# box.net
KiCad netlist of a schematic drawn in EAGLE
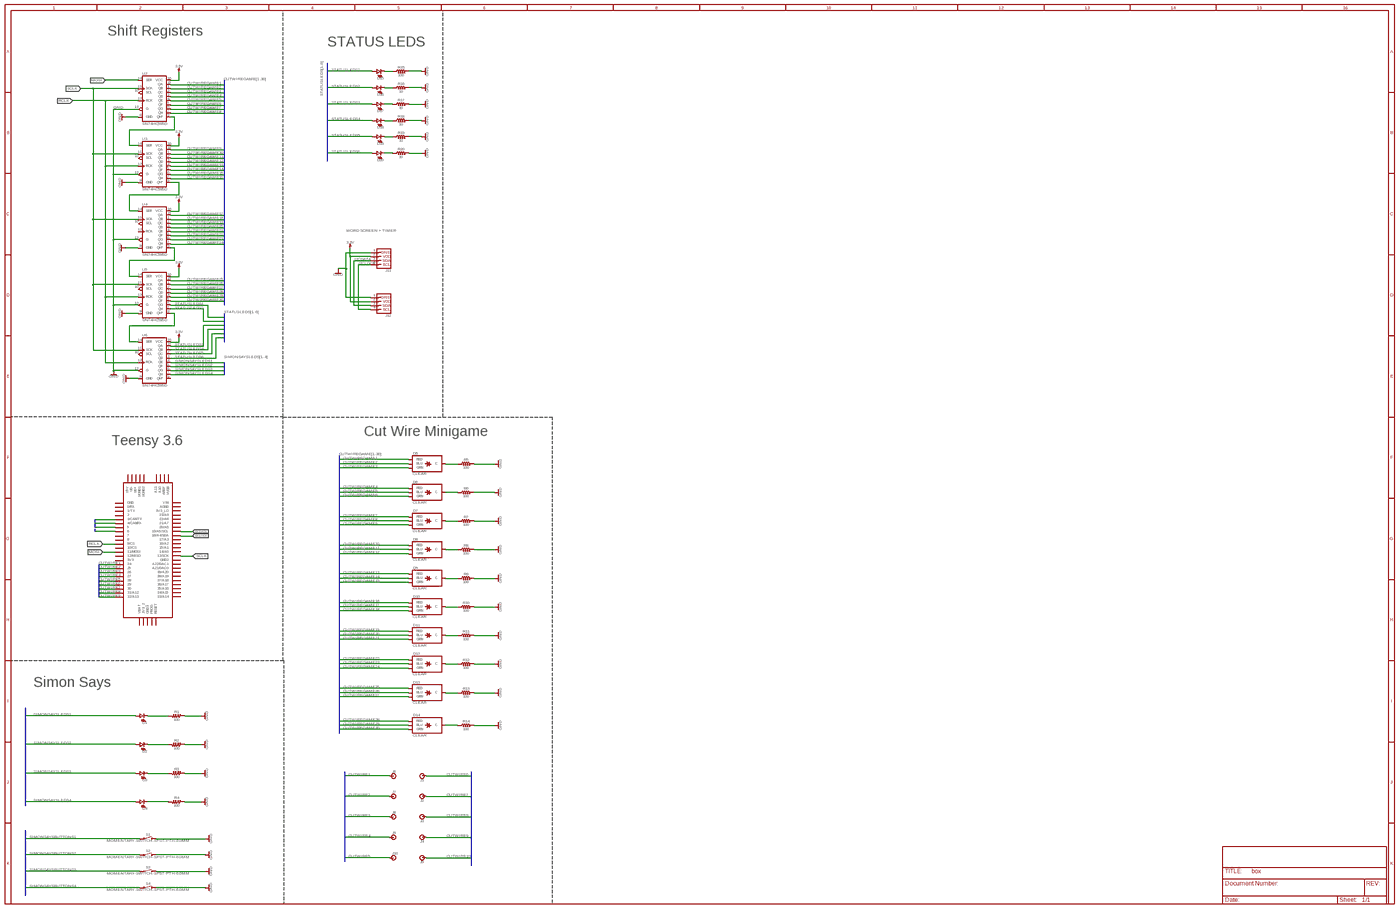
[diagram p0: schematic, sheet 1, overview]
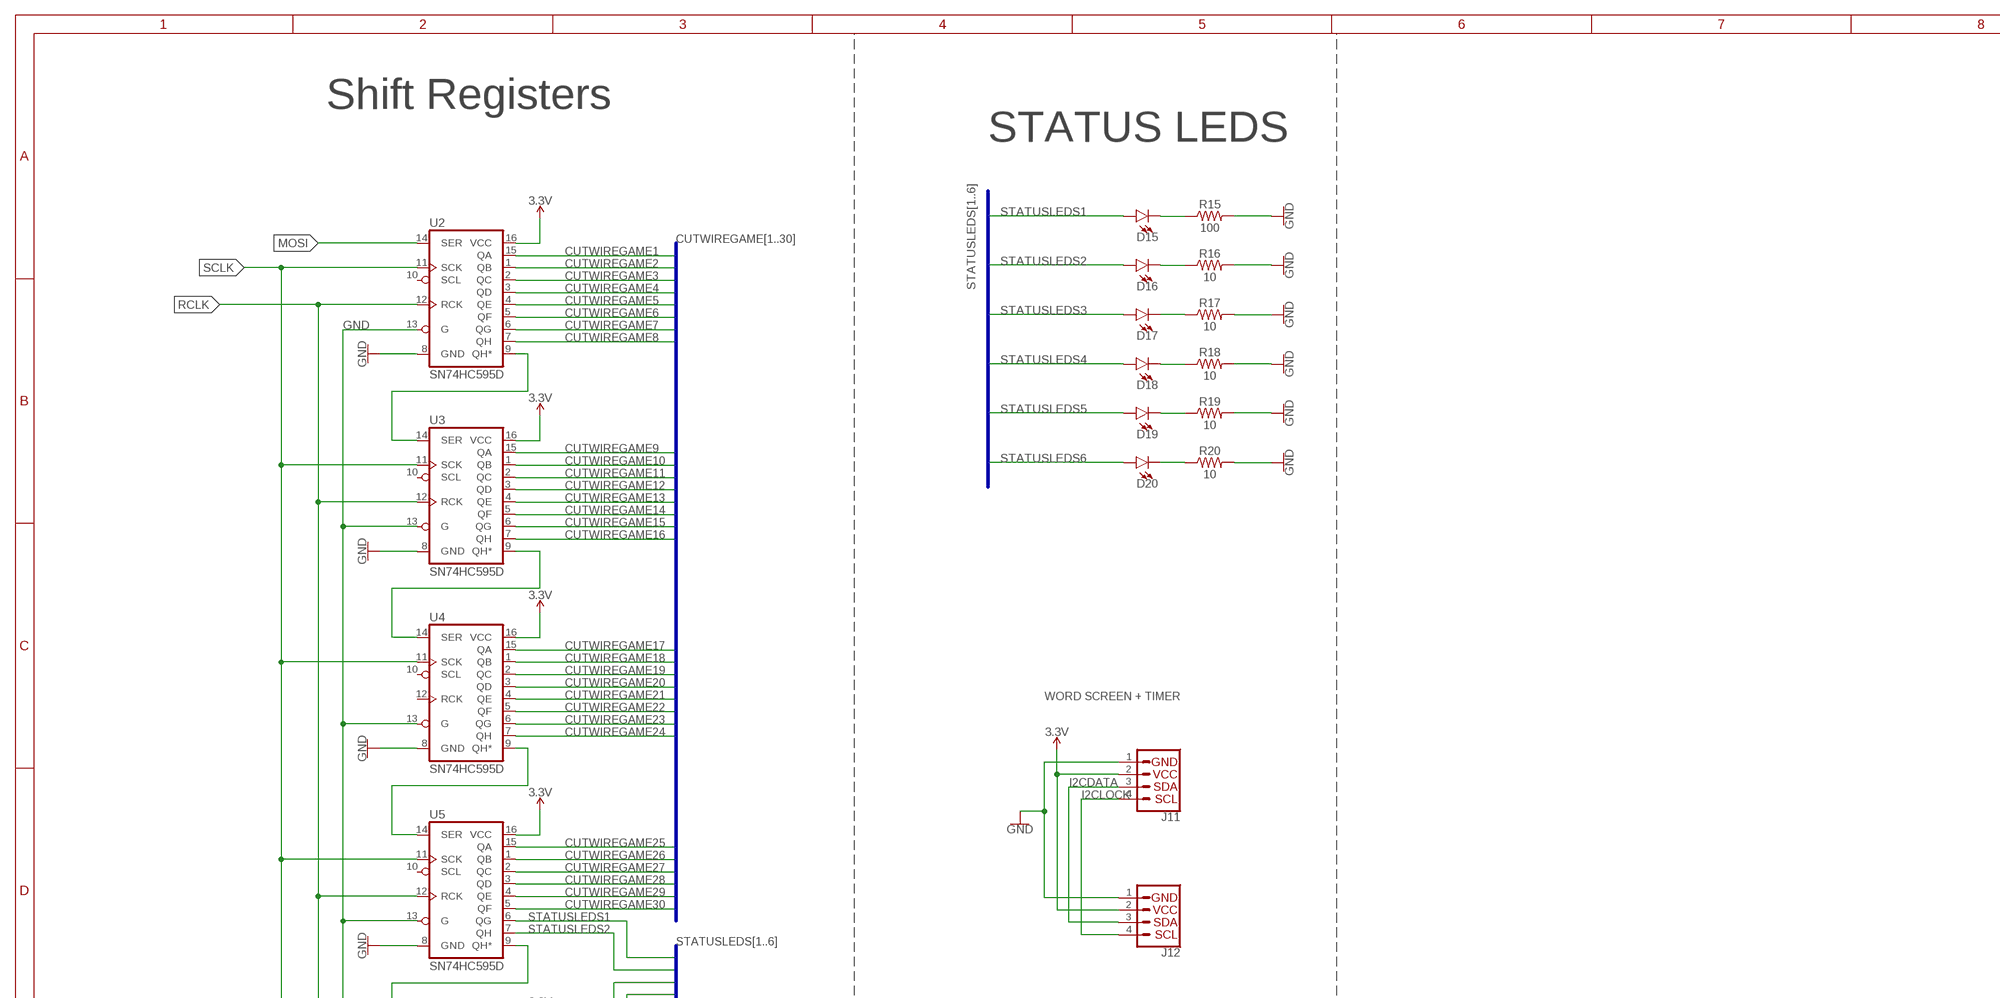
[diagram p1: schematic, sheet 1, part 1 of 4]
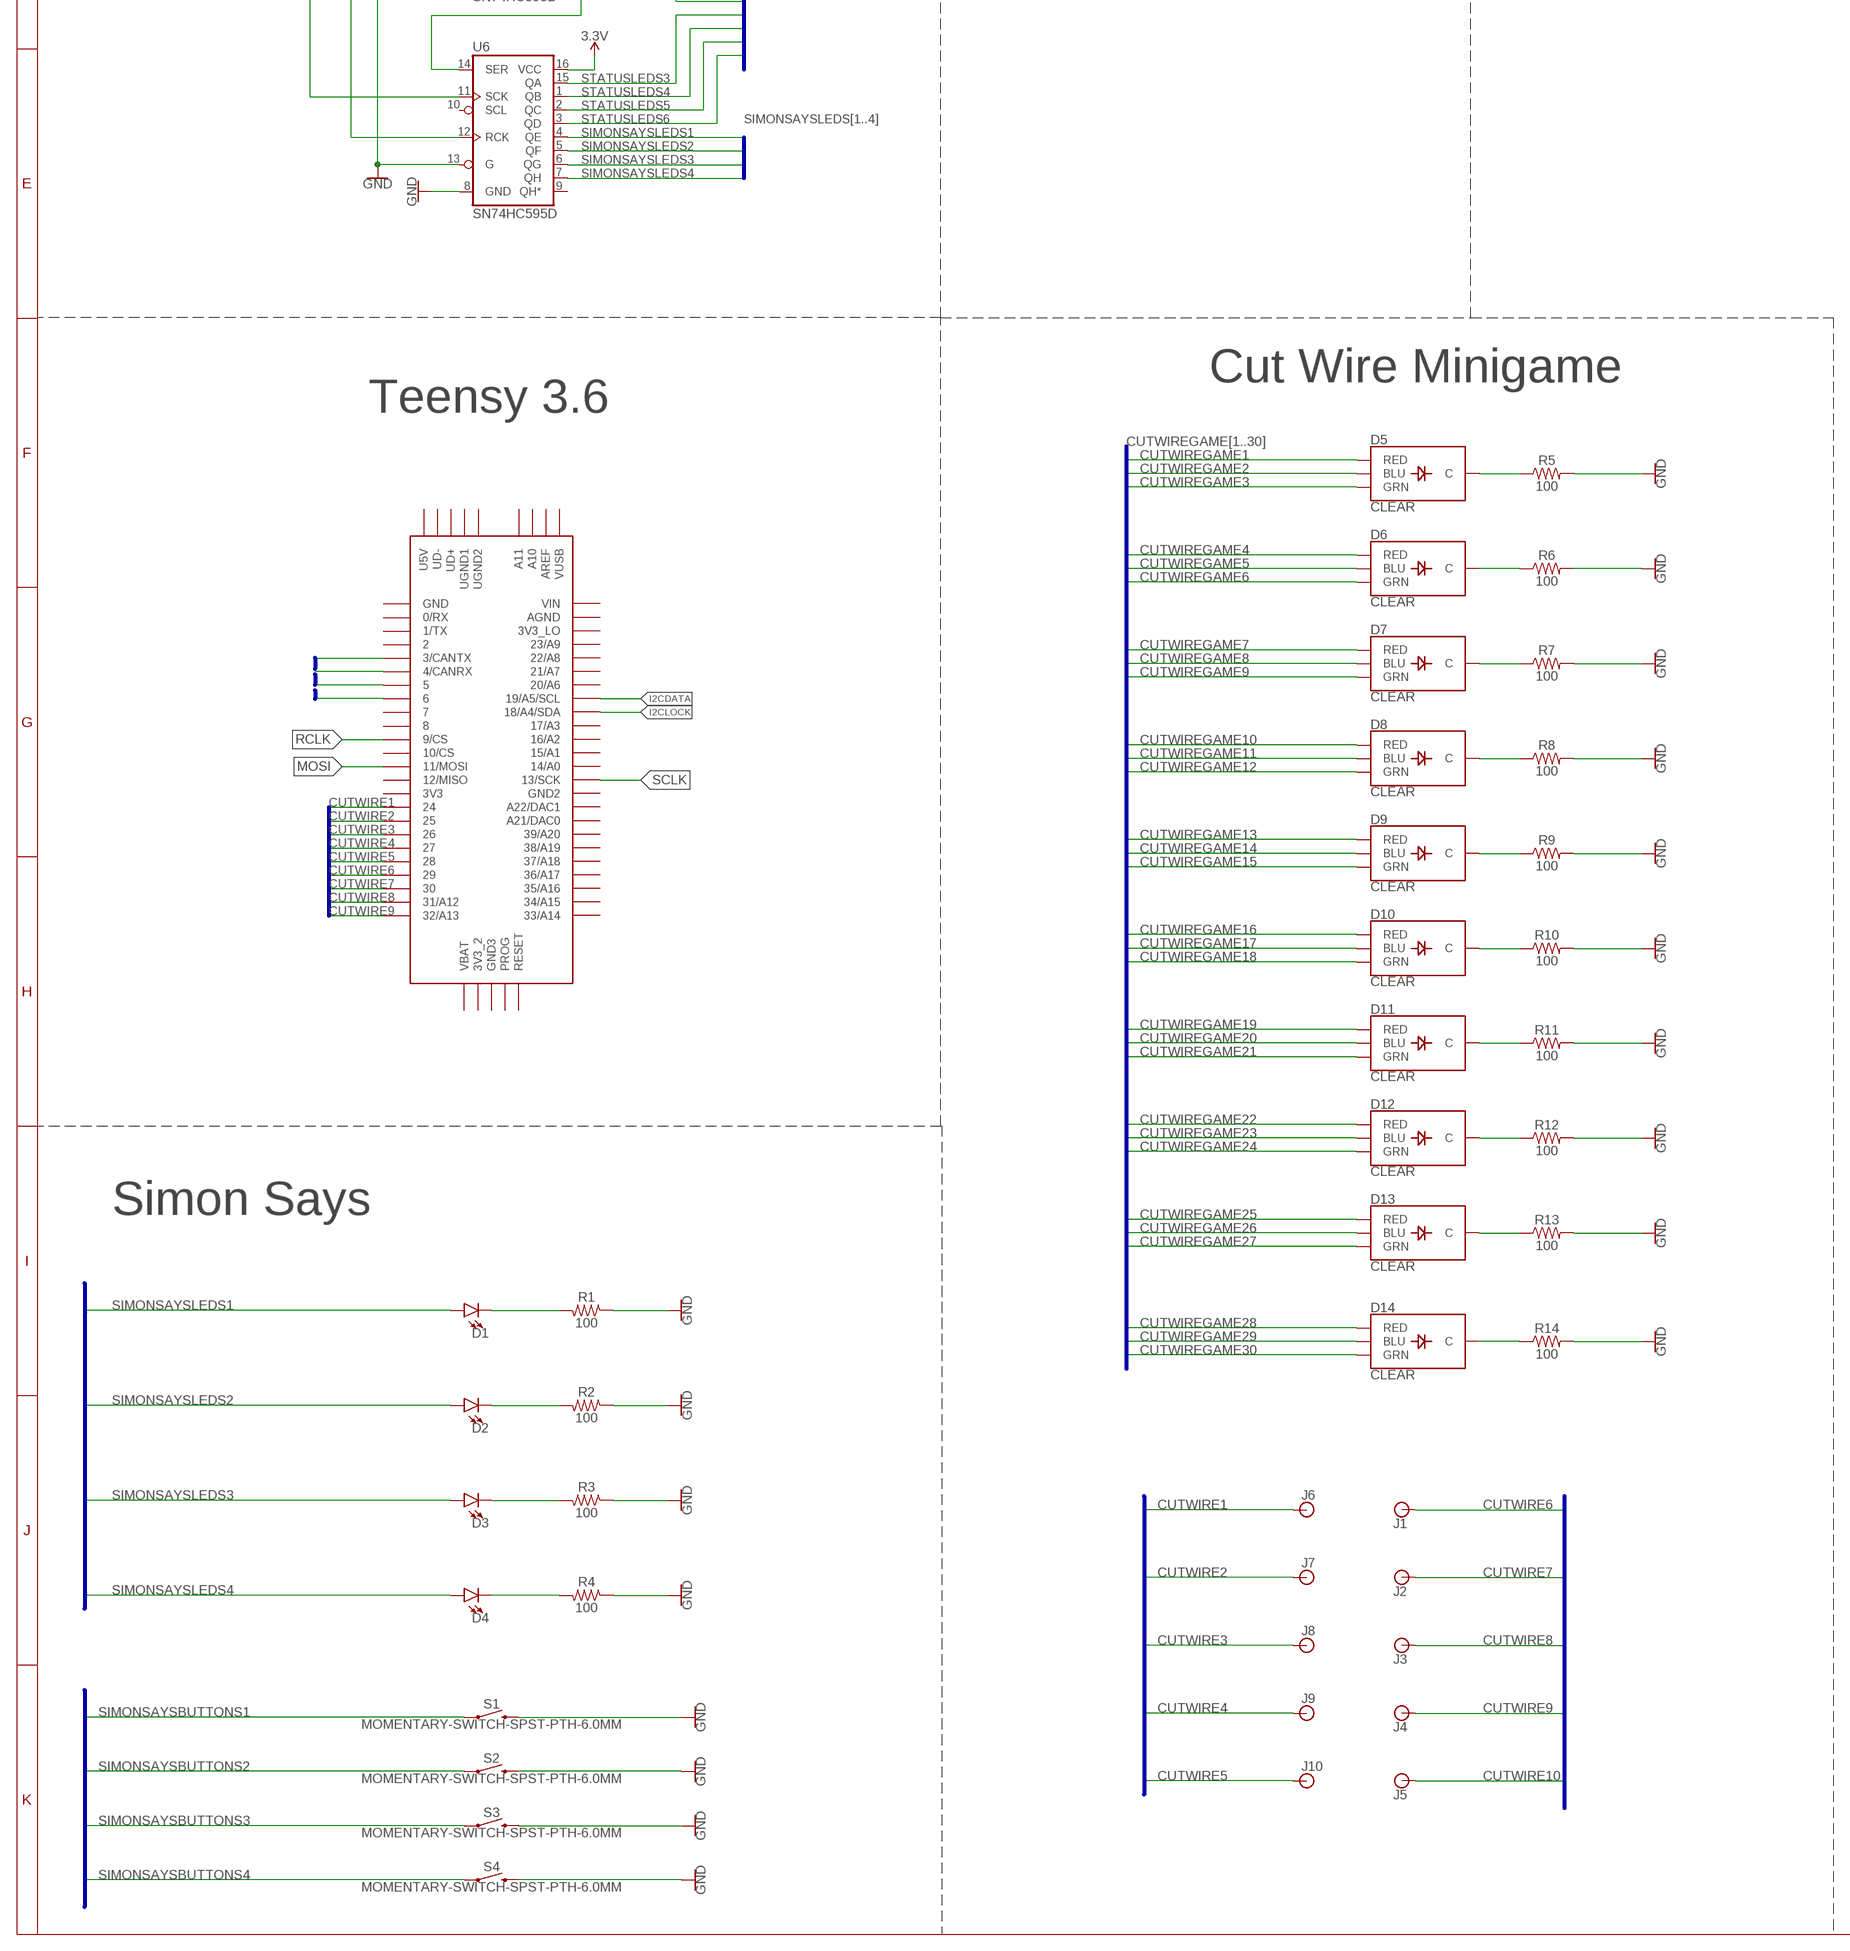
[diagram p2: schematic, sheet 1, part 2 of 4]
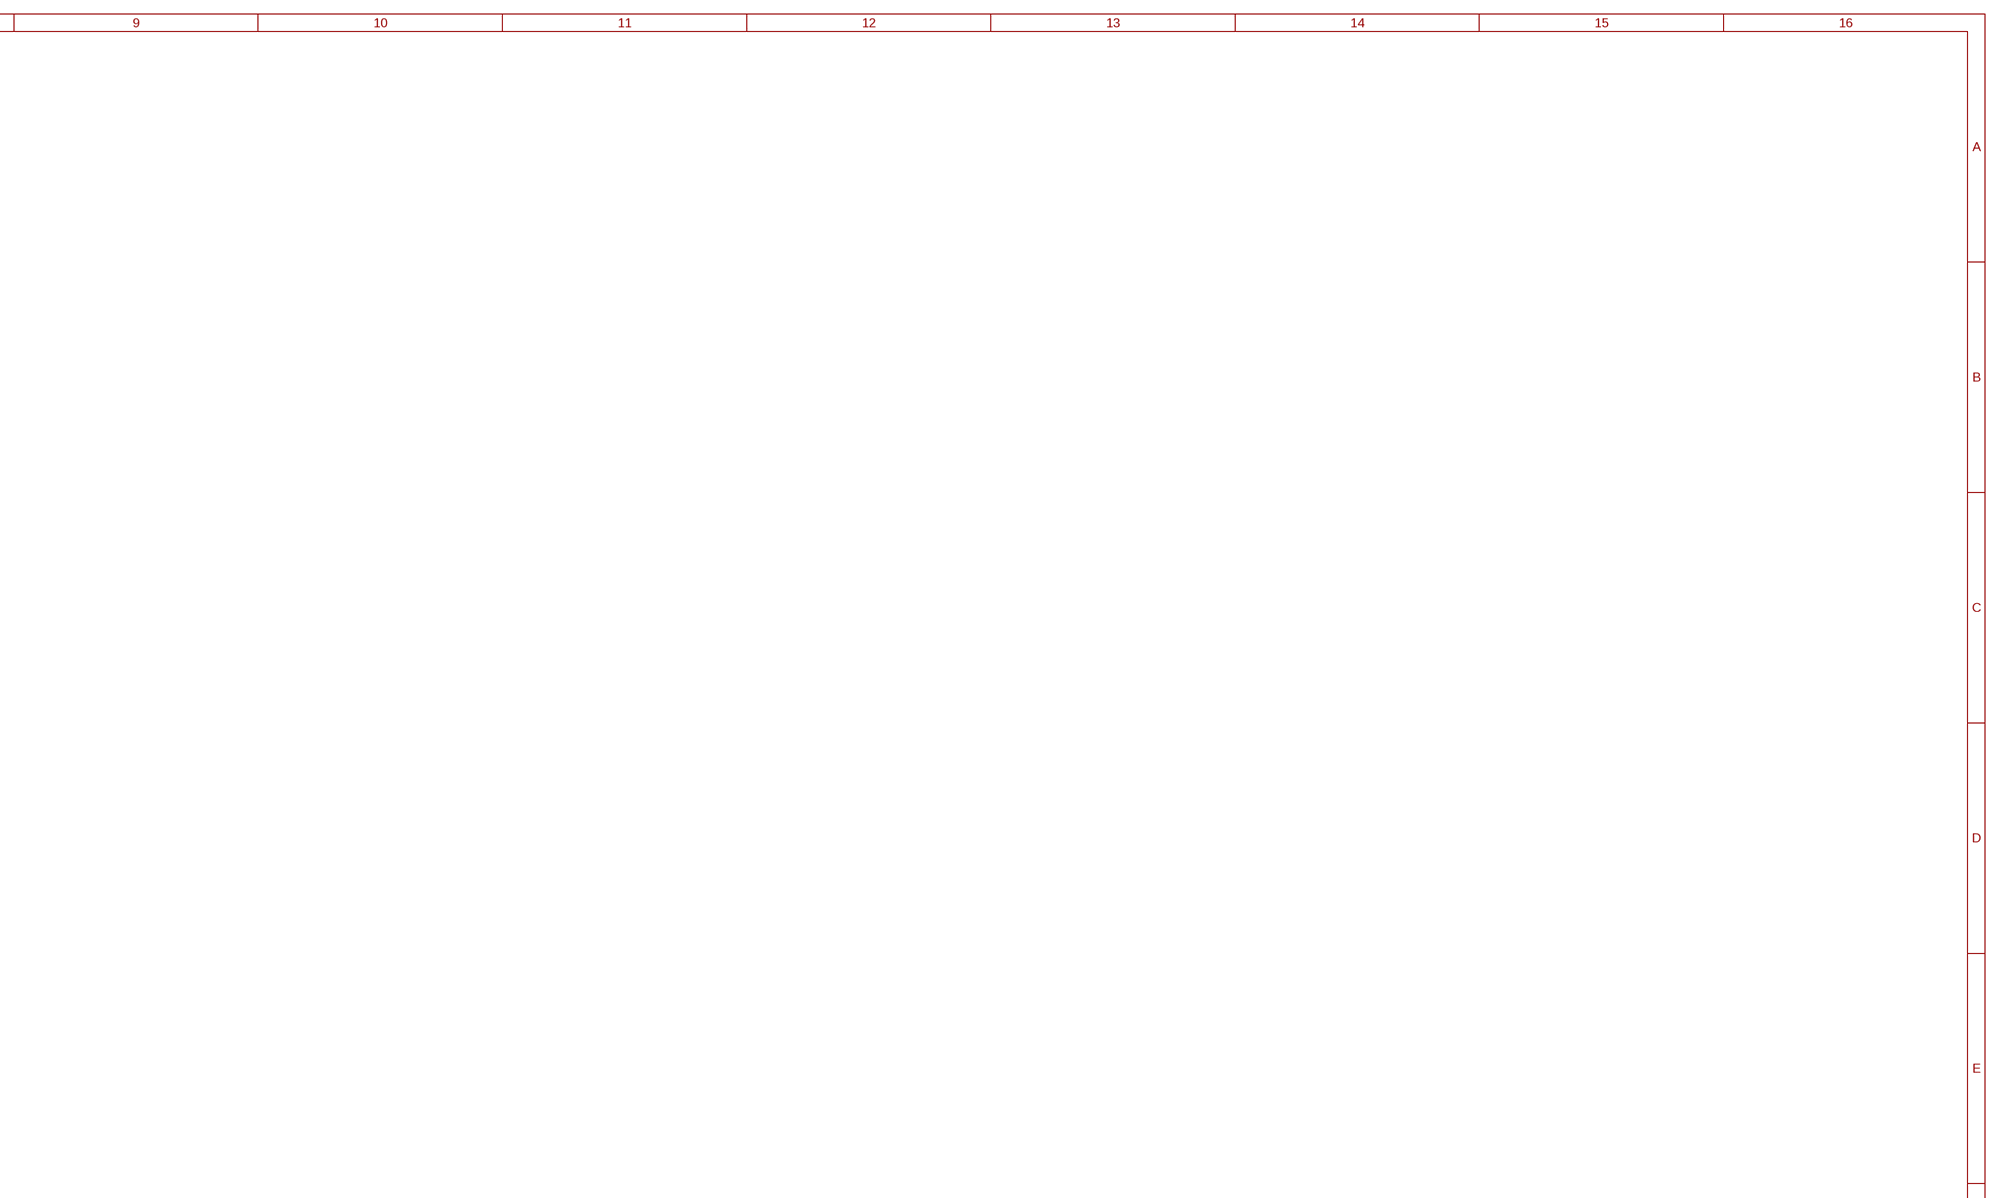
[diagram p3: schematic, sheet 1, part 3 of 4]
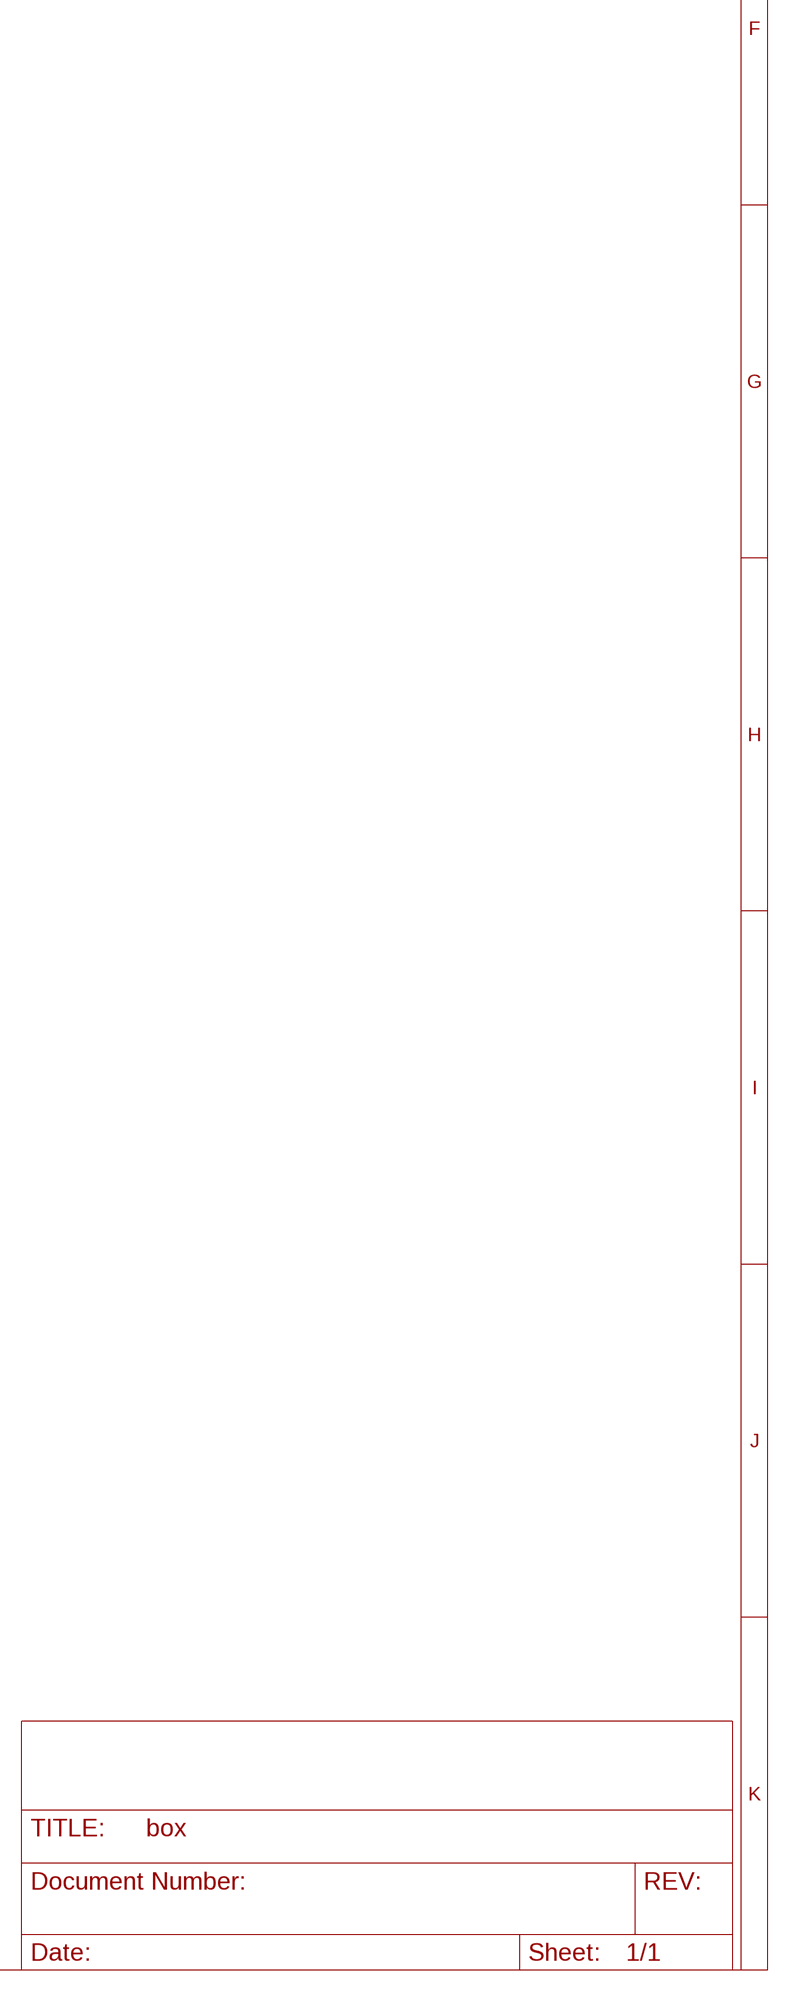
[diagram p4: schematic, sheet 1, part 4 of 4]

(export (version "E")
  (design (tool "Eeschema 10.0.6"))
  (components
    (comp (ref "D1")
      (value "LED3MM")
      (footprint "eagle-import:LED_3MM")
      (libsource (lib "eagle-import") (part "LED3MM"))
    )
    (comp (ref "D2")
      (value "LED3MM")
      (footprint "eagle-import:LED_3MM")
      (libsource (lib "eagle-import") (part "LED3MM"))
    )
    (comp (ref "D3")
      (value "LED3MM")
      (footprint "eagle-import:LED_3MM")
      (libsource (lib "eagle-import") (part "LED3MM"))
    )
    (comp (ref "D4")
      (value "LED3MM")
      (footprint "eagle-import:LED_3MM")
      (libsource (lib "eagle-import") (part "LED3MM"))
    )
    (comp (ref "D5")
      (value "CLEAR")
      (footprint "eagle-import:LED-RGB-THRU")
      (libsource (lib "eagle-import") (part "LED-RGB-CCCLEAR"))
    )
    (comp (ref "D6")
      (value "CLEAR")
      (footprint "eagle-import:LED-RGB-THRU")
      (libsource (lib "eagle-import") (part "LED-RGB-CCCLEAR"))
    )
    (comp (ref "D7")
      (value "CLEAR")
      (footprint "eagle-import:LED-RGB-THRU")
      (libsource (lib "eagle-import") (part "LED-RGB-CCCLEAR"))
    )
    (comp (ref "D8")
      (value "CLEAR")
      (footprint "eagle-import:LED-RGB-THRU")
      (libsource (lib "eagle-import") (part "LED-RGB-CCCLEAR"))
    )
    (comp (ref "D9")
      (value "CLEAR")
      (footprint "eagle-import:LED-RGB-THRU")
      (libsource (lib "eagle-import") (part "LED-RGB-CCCLEAR"))
    )
    (comp (ref "D10")
      (value "CLEAR")
      (footprint "eagle-import:LED-RGB-THRU")
      (libsource (lib "eagle-import") (part "LED-RGB-CCCLEAR"))
    )
    (comp (ref "D11")
      (value "CLEAR")
      (footprint "eagle-import:LED-RGB-THRU")
      (libsource (lib "eagle-import") (part "LED-RGB-CCCLEAR"))
    )
    (comp (ref "D12")
      (value "CLEAR")
      (footprint "eagle-import:LED-RGB-THRU")
      (libsource (lib "eagle-import") (part "LED-RGB-CCCLEAR"))
    )
    (comp (ref "D13")
      (value "CLEAR")
      (footprint "eagle-import:LED-RGB-THRU")
      (libsource (lib "eagle-import") (part "LED-RGB-CCCLEAR"))
    )
    (comp (ref "D14")
      (value "CLEAR")
      (footprint "eagle-import:LED-RGB-THRU")
      (libsource (lib "eagle-import") (part "LED-RGB-CCCLEAR"))
    )
    (comp (ref "D15")
      (value "LED5MM")
      (footprint "eagle-import:LED_5MM")
      (libsource (lib "eagle-import") (part "LED5MM"))
    )
    (comp (ref "D16")
      (value "LED5MM")
      (footprint "eagle-import:LED_5MM")
      (libsource (lib "eagle-import") (part "LED5MM"))
    )
    (comp (ref "D17")
      (value "LED5MM")
      (footprint "eagle-import:LED_5MM")
      (libsource (lib "eagle-import") (part "LED5MM"))
    )
    (comp (ref "D18")
      (value "LED5MM")
      (footprint "eagle-import:LED_5MM")
      (libsource (lib "eagle-import") (part "LED5MM"))
    )
    (comp (ref "D19")
      (value "LED5MM")
      (footprint "eagle-import:LED_5MM")
      (libsource (lib "eagle-import") (part "LED5MM"))
    )
    (comp (ref "D20")
      (value "LED5MM")
      (footprint "eagle-import:LED_5MM")
      (libsource (lib "eagle-import") (part "LED5MM"))
    )
    (comp (ref "J1")
      (value "BANANA_CONN")
      (footprint "eagle-import:BANANA_CONN")
      (libsource (lib "eagle-import") (part "BANANA_CONN"))
    )
    (comp (ref "J2")
      (value "BANANA_CONN")
      (footprint "eagle-import:BANANA_CONN")
      (libsource (lib "eagle-import") (part "BANANA_CONN"))
    )
    (comp (ref "J3")
      (value "BANANA_CONN")
      (footprint "eagle-import:BANANA_CONN")
      (libsource (lib "eagle-import") (part "BANANA_CONN"))
    )
    (comp (ref "J4")
      (value "BANANA_CONN")
      (footprint "eagle-import:BANANA_CONN")
      (libsource (lib "eagle-import") (part "BANANA_CONN"))
    )
    (comp (ref "J5")
      (value "BANANA_CONN")
      (footprint "eagle-import:BANANA_CONN")
      (libsource (lib "eagle-import") (part "BANANA_CONN"))
    )
    (comp (ref "J6")
      (value "BANANA_CONN")
      (footprint "eagle-import:BANANA_CONN")
      (libsource (lib "eagle-import") (part "BANANA_CONN"))
    )
    (comp (ref "J7")
      (value "BANANA_CONN")
      (footprint "eagle-import:BANANA_CONN")
      (libsource (lib "eagle-import") (part "BANANA_CONN"))
    )
    (comp (ref "J8")
      (value "BANANA_CONN")
      (footprint "eagle-import:BANANA_CONN")
      (libsource (lib "eagle-import") (part "BANANA_CONN"))
    )
    (comp (ref "J9")
      (value "BANANA_CONN")
      (footprint "eagle-import:BANANA_CONN")
      (libsource (lib "eagle-import") (part "BANANA_CONN"))
    )
    (comp (ref "J10")
      (value "BANANA_CONN")
      (footprint "eagle-import:BANANA_CONN")
      (libsource (lib "eagle-import") (part "BANANA_CONN"))
    )
    (comp (ref "J11")
      (value "I2C_STANDARD")
      (footprint "eagle-import:1X04")
      (libsource (lib "eagle-import") (part "I2C_STANDARD"))
    )
    (comp (ref "J12")
      (value "I2C_STANDARD")
      (footprint "eagle-import:1X04")
      (libsource (lib "eagle-import") (part "I2C_STANDARD"))
    )
    (comp (ref "R1")
      (value "100")
      (footprint "eagle-import:AXIAL-0.3EZ")
      (libsource (lib "eagle-import") (part "100OHM-HORIZ_KIT-1/4W-1%"))
    )
    (comp (ref "R2")
      (value "100")
      (footprint "eagle-import:AXIAL-0.3EZ")
      (libsource (lib "eagle-import") (part "100OHM-HORIZ_KIT-1/4W-1%"))
    )
    (comp (ref "R3")
      (value "100")
      (footprint "eagle-import:AXIAL-0.3EZ")
      (libsource (lib "eagle-import") (part "100OHM-HORIZ_KIT-1/4W-1%"))
    )
    (comp (ref "R4")
      (value "100")
      (footprint "eagle-import:AXIAL-0.3EZ")
      (libsource (lib "eagle-import") (part "100OHM-HORIZ_KIT-1/4W-1%"))
    )
    (comp (ref "R5")
      (value "100")
      (footprint "eagle-import:AXIAL-0.3")
      (libsource (lib "eagle-import") (part "100OHM-HORIZ-1/4W-1%"))
    )
    (comp (ref "R6")
      (value "100")
      (footprint "eagle-import:AXIAL-0.3")
      (libsource (lib "eagle-import") (part "100OHM-HORIZ-1/4W-1%"))
    )
    (comp (ref "R7")
      (value "100")
      (footprint "eagle-import:AXIAL-0.3")
      (libsource (lib "eagle-import") (part "100OHM-HORIZ-1/4W-1%"))
    )
    (comp (ref "R8")
      (value "100")
      (footprint "eagle-import:AXIAL-0.3")
      (libsource (lib "eagle-import") (part "100OHM-HORIZ-1/4W-1%"))
    )
    (comp (ref "R9")
      (value "100")
      (footprint "eagle-import:AXIAL-0.3")
      (libsource (lib "eagle-import") (part "100OHM-HORIZ-1/4W-1%"))
    )
    (comp (ref "R10")
      (value "100")
      (footprint "eagle-import:AXIAL-0.3")
      (libsource (lib "eagle-import") (part "100OHM-HORIZ-1/4W-1%"))
    )
    (comp (ref "R11")
      (value "100")
      (footprint "eagle-import:AXIAL-0.3")
      (libsource (lib "eagle-import") (part "100OHM-HORIZ-1/4W-1%"))
    )
    (comp (ref "R12")
      (value "100")
      (footprint "eagle-import:AXIAL-0.3")
      (libsource (lib "eagle-import") (part "100OHM-HORIZ-1/4W-1%"))
    )
    (comp (ref "R13")
      (value "100")
      (footprint "eagle-import:AXIAL-0.3")
      (libsource (lib "eagle-import") (part "100OHM-HORIZ-1/4W-1%"))
    )
    (comp (ref "R14")
      (value "100")
      (footprint "eagle-import:AXIAL-0.3")
      (libsource (lib "eagle-import") (part "100OHM-HORIZ-1/4W-1%"))
    )
    (comp (ref "R15")
      (value "100")
      (footprint "eagle-import:AXIAL-0.3")
      (libsource (lib "eagle-import") (part "100OHM-HORIZ-1/4W-1%"))
    )
    (comp (ref "R16")
      (value "10")
      (footprint "eagle-import:AXIAL-0.3")
      (libsource (lib "eagle-import") (part "10OHM-HORIZ-1/4W-1%"))
    )
    (comp (ref "R17")
      (value "10")
      (footprint "eagle-import:AXIAL-0.3")
      (libsource (lib "eagle-import") (part "10OHM-HORIZ-1/4W-1%"))
    )
    (comp (ref "R18")
      (value "10")
      (footprint "eagle-import:AXIAL-0.3")
      (libsource (lib "eagle-import") (part "10OHM-HORIZ-1/4W-1%"))
    )
    (comp (ref "R19")
      (value "10")
      (footprint "eagle-import:AXIAL-0.3")
      (libsource (lib "eagle-import") (part "10OHM-HORIZ-1/4W-1%"))
    )
    (comp (ref "R20")
      (value "10")
      (footprint "eagle-import:AXIAL-0.3")
      (libsource (lib "eagle-import") (part "10OHM-HORIZ-1/4W-1%"))
    )
    (comp (ref "S1")
      (value "MOMENTARY-SWITCH-SPST-PTH-6.0MM")
      (footprint "eagle-import:TACTILE_SWITCH_PTH_6.0MM")
      (libsource (lib "eagle-import") (part "MOMENTARY-SWITCH-SPST-PTH-6.0MM"))
    )
    (comp (ref "S2")
      (value "MOMENTARY-SWITCH-SPST-PTH-6.0MM")
      (footprint "eagle-import:TACTILE_SWITCH_PTH_6.0MM")
      (libsource (lib "eagle-import") (part "MOMENTARY-SWITCH-SPST-PTH-6.0MM"))
    )
    (comp (ref "S3")
      (value "MOMENTARY-SWITCH-SPST-PTH-6.0MM")
      (footprint "eagle-import:TACTILE_SWITCH_PTH_6.0MM")
      (libsource (lib "eagle-import") (part "MOMENTARY-SWITCH-SPST-PTH-6.0MM"))
    )
    (comp (ref "S4")
      (value "MOMENTARY-SWITCH-SPST-PTH-6.0MM")
      (footprint "eagle-import:TACTILE_SWITCH_PTH_6.0MM")
      (libsource (lib "eagle-import") (part "MOMENTARY-SWITCH-SPST-PTH-6.0MM"))
    )
    (comp (ref "U$1")
      (value "TEENSY_3.5/3.6")
      (footprint "eagle-import:TEENSY_3.5_3.6")
      (libsource (lib "eagle-import") (part "TEENSY_3.5/3.6"))
    )
    (comp (ref "U2")
      (value "SN74HC595D")
      (footprint "eagle-import:SO16")
      (libsource (lib "eagle-import") (part "74595DHC"))
    )
    (comp (ref "U3")
      (value "SN74HC595D")
      (footprint "eagle-import:SO16")
      (libsource (lib "eagle-import") (part "74595DHC"))
    )
    (comp (ref "U4")
      (value "SN74HC595D")
      (footprint "eagle-import:SO16")
      (libsource (lib "eagle-import") (part "74595DHC"))
    )
    (comp (ref "U5")
      (value "SN74HC595D")
      (footprint "eagle-import:SO16")
      (libsource (lib "eagle-import") (part "74595DHC"))
    )
    (comp (ref "U6")
      (value "SN74HC595D")
      (footprint "eagle-import:SO16")
      (libsource (lib "eagle-import") (part "74595DHC"))
    )
  )
  (nets
    (net (code "1") (name "/CUTWIRE1") (class "Default")
      (node (ref "J6") (pin "P$1") (pinfunction "1_P$1") (pintype "passive"))
      (node (ref "U$1") (pin "24") (pinfunction "24_24") (pintype "bidirectional"))
    )
    (net (code "2") (name "/CUTWIRE2") (class "Default")
      (node (ref "J7") (pin "P$1") (pinfunction "1_P$1") (pintype "passive"))
      (node (ref "U$1") (pin "25") (pinfunction "25_25") (pintype "bidirectional"))
    )
    (net (code "3") (name "/CUTWIRE3") (class "Default")
      (node (ref "J8") (pin "P$1") (pinfunction "1_P$1") (pintype "passive"))
      (node (ref "U$1") (pin "26") (pinfunction "26_26") (pintype "bidirectional"))
    )
    (net (code "4") (name "/CUTWIRE4") (class "Default")
      (node (ref "J9") (pin "P$1") (pinfunction "1_P$1") (pintype "passive"))
      (node (ref "U$1") (pin "27") (pinfunction "27_27") (pintype "bidirectional"))
    )
    (net (code "5") (name "/CUTWIRE5") (class "Default")
      (node (ref "J10") (pin "P$1") (pinfunction "1_P$1") (pintype "passive"))
      (node (ref "U$1") (pin "28") (pinfunction "28_28") (pintype "bidirectional"))
    )
    (net (code "6") (name "/CUTWIRE6") (class "Default")
      (node (ref "J1") (pin "P$1") (pinfunction "1_P$1") (pintype "passive"))
      (node (ref "U$1") (pin "29") (pinfunction "29_29") (pintype "bidirectional"))
    )
    (net (code "7") (name "/CUTWIRE7") (class "Default")
      (node (ref "J2") (pin "P$1") (pinfunction "1_P$1") (pintype "passive"))
      (node (ref "U$1") (pin "30") (pinfunction "30_30") (pintype "bidirectional"))
    )
    (net (code "8") (name "/CUTWIRE8") (class "Default")
      (node (ref "J3") (pin "P$1") (pinfunction "1_P$1") (pintype "passive"))
      (node (ref "U$1") (pin "31/A12") (pinfunction "31/A12_31/A12") (pintype "bidirectional"))
    )
    (net (code "9") (name "/CUTWIRE9") (class "Default")
      (node (ref "J4") (pin "P$1") (pinfunction "1_P$1") (pintype "passive"))
      (node (ref "U$1") (pin "32/A13") (pinfunction "32/A13_32/A13") (pintype "bidirectional"))
    )
    (net (code "10") (name "/CUTWIRE10") (class "Default")
      (node (ref "J5") (pin "P$1") (pinfunction "1_P$1") (pintype "passive"))
    )
    (net (code "11") (name "/CUTWIREGAME1") (class "Default")
      (node (ref "D5") (pin "1") (pinfunction "RED_1") (pintype "bidirectional"))
      (node (ref "U2") (pin "15") (pinfunction "QA_15") (pintype "tri_state"))
    )
    (net (code "12") (name "/CUTWIREGAME2") (class "Default")
      (node (ref "D5") (pin "4") (pinfunction "BLU_4") (pintype "bidirectional"))
      (node (ref "U2") (pin "1") (pinfunction "QB_1") (pintype "tri_state"))
    )
    (net (code "13") (name "/CUTWIREGAME3") (class "Default")
      (node (ref "D5") (pin "3") (pinfunction "GRN_3") (pintype "bidirectional"))
      (node (ref "U2") (pin "2") (pinfunction "QC_2") (pintype "tri_state"))
    )
    (net (code "14") (name "/CUTWIREGAME4") (class "Default")
      (node (ref "D6") (pin "1") (pinfunction "RED_1") (pintype "bidirectional"))
      (node (ref "U2") (pin "3") (pinfunction "QD_3") (pintype "tri_state"))
    )
    (net (code "15") (name "/CUTWIREGAME5") (class "Default")
      (node (ref "D6") (pin "4") (pinfunction "BLU_4") (pintype "bidirectional"))
      (node (ref "U2") (pin "4") (pinfunction "QE_4") (pintype "tri_state"))
    )
    (net (code "16") (name "/CUTWIREGAME6") (class "Default")
      (node (ref "D6") (pin "3") (pinfunction "GRN_3") (pintype "bidirectional"))
      (node (ref "U2") (pin "5") (pinfunction "QF_5") (pintype "tri_state"))
    )
    (net (code "17") (name "/CUTWIREGAME7") (class "Default")
      (node (ref "D7") (pin "1") (pinfunction "RED_1") (pintype "bidirectional"))
      (node (ref "U2") (pin "6") (pinfunction "QG_6") (pintype "tri_state"))
    )
    (net (code "18") (name "/CUTWIREGAME8") (class "Default")
      (node (ref "D7") (pin "4") (pinfunction "BLU_4") (pintype "bidirectional"))
      (node (ref "U2") (pin "7") (pinfunction "QH_7") (pintype "tri_state"))
    )
    (net (code "19") (name "/CUTWIREGAME9") (class "Default")
      (node (ref "D7") (pin "3") (pinfunction "GRN_3") (pintype "bidirectional"))
      (node (ref "U3") (pin "15") (pinfunction "QA_15") (pintype "tri_state"))
    )
    (net (code "20") (name "/CUTWIREGAME10") (class "Default")
      (node (ref "D8") (pin "1") (pinfunction "RED_1") (pintype "bidirectional"))
      (node (ref "U3") (pin "1") (pinfunction "QB_1") (pintype "tri_state"))
    )
    (net (code "21") (name "/CUTWIREGAME11") (class "Default")
      (node (ref "D8") (pin "4") (pinfunction "BLU_4") (pintype "bidirectional"))
      (node (ref "U3") (pin "2") (pinfunction "QC_2") (pintype "tri_state"))
    )
    (net (code "22") (name "/CUTWIREGAME12") (class "Default")
      (node (ref "D8") (pin "3") (pinfunction "GRN_3") (pintype "bidirectional"))
      (node (ref "U3") (pin "3") (pinfunction "QD_3") (pintype "tri_state"))
    )
    (net (code "23") (name "/CUTWIREGAME13") (class "Default")
      (node (ref "D9") (pin "1") (pinfunction "RED_1") (pintype "bidirectional"))
      (node (ref "U3") (pin "4") (pinfunction "QE_4") (pintype "tri_state"))
    )
    (net (code "24") (name "/CUTWIREGAME14") (class "Default")
      (node (ref "D9") (pin "4") (pinfunction "BLU_4") (pintype "bidirectional"))
      (node (ref "U3") (pin "5") (pinfunction "QF_5") (pintype "tri_state"))
    )
    (net (code "25") (name "/CUTWIREGAME15") (class "Default")
      (node (ref "D9") (pin "3") (pinfunction "GRN_3") (pintype "bidirectional"))
      (node (ref "U3") (pin "6") (pinfunction "QG_6") (pintype "tri_state"))
    )
    (net (code "26") (name "/CUTWIREGAME16") (class "Default")
      (node (ref "D10") (pin "1") (pinfunction "RED_1") (pintype "bidirectional"))
      (node (ref "U3") (pin "7") (pinfunction "QH_7") (pintype "tri_state"))
    )
    (net (code "27") (name "/CUTWIREGAME17") (class "Default")
      (node (ref "D10") (pin "4") (pinfunction "BLU_4") (pintype "bidirectional"))
      (node (ref "U4") (pin "15") (pinfunction "QA_15") (pintype "tri_state"))
    )
    (net (code "28") (name "/CUTWIREGAME18") (class "Default")
      (node (ref "D10") (pin "3") (pinfunction "GRN_3") (pintype "bidirectional"))
      (node (ref "U4") (pin "1") (pinfunction "QB_1") (pintype "tri_state"))
    )
    (net (code "29") (name "/CUTWIREGAME19") (class "Default")
      (node (ref "D11") (pin "1") (pinfunction "RED_1") (pintype "bidirectional"))
      (node (ref "U4") (pin "2") (pinfunction "QC_2") (pintype "tri_state"))
    )
    (net (code "30") (name "/CUTWIREGAME20") (class "Default")
      (node (ref "D11") (pin "4") (pinfunction "BLU_4") (pintype "bidirectional"))
      (node (ref "U4") (pin "3") (pinfunction "QD_3") (pintype "tri_state"))
    )
    (net (code "31") (name "/CUTWIREGAME21") (class "Default")
      (node (ref "D11") (pin "3") (pinfunction "GRN_3") (pintype "bidirectional"))
      (node (ref "U4") (pin "4") (pinfunction "QE_4") (pintype "tri_state"))
    )
    (net (code "32") (name "/CUTWIREGAME22") (class "Default")
      (node (ref "D12") (pin "1") (pinfunction "RED_1") (pintype "bidirectional"))
      (node (ref "U4") (pin "5") (pinfunction "QF_5") (pintype "tri_state"))
    )
    (net (code "33") (name "/CUTWIREGAME23") (class "Default")
      (node (ref "D12") (pin "4") (pinfunction "BLU_4") (pintype "bidirectional"))
      (node (ref "U4") (pin "6") (pinfunction "QG_6") (pintype "tri_state"))
    )
    (net (code "34") (name "/CUTWIREGAME24") (class "Default")
      (node (ref "D12") (pin "3") (pinfunction "GRN_3") (pintype "bidirectional"))
      (node (ref "U4") (pin "7") (pinfunction "QH_7") (pintype "tri_state"))
    )
    (net (code "35") (name "/CUTWIREGAME25") (class "Default")
      (node (ref "D13") (pin "1") (pinfunction "RED_1") (pintype "bidirectional"))
      (node (ref "U5") (pin "15") (pinfunction "QA_15") (pintype "tri_state"))
    )
    (net (code "36") (name "/CUTWIREGAME26") (class "Default")
      (node (ref "D13") (pin "4") (pinfunction "BLU_4") (pintype "bidirectional"))
      (node (ref "U5") (pin "1") (pinfunction "QB_1") (pintype "tri_state"))
    )
    (net (code "37") (name "/CUTWIREGAME27") (class "Default")
      (node (ref "D13") (pin "3") (pinfunction "GRN_3") (pintype "bidirectional"))
      (node (ref "U5") (pin "2") (pinfunction "QC_2") (pintype "tri_state"))
    )
    (net (code "38") (name "/CUTWIREGAME28") (class "Default")
      (node (ref "D14") (pin "1") (pinfunction "RED_1") (pintype "bidirectional"))
      (node (ref "U5") (pin "3") (pinfunction "QD_3") (pintype "tri_state"))
    )
    (net (code "39") (name "/CUTWIREGAME29") (class "Default")
      (node (ref "D14") (pin "4") (pinfunction "BLU_4") (pintype "bidirectional"))
      (node (ref "U5") (pin "4") (pinfunction "QE_4") (pintype "tri_state"))
    )
    (net (code "40") (name "/CUTWIREGAME30") (class "Default")
      (node (ref "D14") (pin "3") (pinfunction "GRN_3") (pintype "bidirectional"))
      (node (ref "U5") (pin "5") (pinfunction "QF_5") (pintype "tri_state"))
    )
    (net (code "42") (name "/SIMONSAYSBUTTONS1") (class "Default")
      (node (ref "S1") (pin "1") (pinfunction "1_1") (pintype "passive"))
      (node (ref "U$1") (pin "3/CANTX") (pinfunction "3/CANTX_3/CANTX") (pintype "bidirectional"))
    )
    (net (code "43") (name "/SIMONSAYSBUTTONS2") (class "Default")
      (node (ref "S2") (pin "1") (pinfunction "1_1") (pintype "passive"))
      (node (ref "U$1") (pin "4/CANRX") (pinfunction "4/CANRX_4/CANRX") (pintype "bidirectional"))
    )
    (net (code "44") (name "/SIMONSAYSBUTTONS3") (class "Default")
      (node (ref "S3") (pin "1") (pinfunction "1_1") (pintype "passive"))
      (node (ref "U$1") (pin "5") (pinfunction "5_5") (pintype "bidirectional"))
    )
    (net (code "45") (name "/SIMONSAYSBUTTONS4") (class "Default")
      (node (ref "S4") (pin "1") (pinfunction "1_1") (pintype "passive"))
      (node (ref "U$1") (pin "6") (pinfunction "6_6") (pintype "bidirectional"))
    )
    (net (code "47") (name "/SIMONSAYSLEDS1") (class "Default")
      (node (ref "D1") (pin "A") (pinfunction "A_A") (pintype "passive"))
      (node (ref "U6") (pin "4") (pinfunction "QE_4") (pintype "tri_state"))
    )
    (net (code "48") (name "/SIMONSAYSLEDS2") (class "Default")
      (node (ref "D2") (pin "A") (pinfunction "A_A") (pintype "passive"))
      (node (ref "U6") (pin "5") (pinfunction "QF_5") (pintype "tri_state"))
    )
    (net (code "49") (name "/SIMONSAYSLEDS3") (class "Default")
      (node (ref "D3") (pin "A") (pinfunction "A_A") (pintype "passive"))
      (node (ref "U6") (pin "6") (pinfunction "QG_6") (pintype "tri_state"))
    )
    (net (code "50") (name "/SIMONSAYSLEDS4") (class "Default")
      (node (ref "D4") (pin "A") (pinfunction "A_A") (pintype "passive"))
      (node (ref "U6") (pin "7") (pinfunction "QH_7") (pintype "tri_state"))
    )
    (net (code "52") (name "/STATUSLEDS1") (class "Default")
      (node (ref "D15") (pin "A") (pinfunction "A_A") (pintype "passive"))
      (node (ref "U5") (pin "6") (pinfunction "QG_6") (pintype "tri_state"))
    )
    (net (code "53") (name "/STATUSLEDS2") (class "Default")
      (node (ref "D16") (pin "A") (pinfunction "A_A") (pintype "passive"))
      (node (ref "U5") (pin "7") (pinfunction "QH_7") (pintype "tri_state"))
    )
    (net (code "54") (name "/STATUSLEDS3") (class "Default")
      (node (ref "D17") (pin "A") (pinfunction "A_A") (pintype "passive"))
      (node (ref "U6") (pin "15") (pinfunction "QA_15") (pintype "tri_state"))
    )
    (net (code "55") (name "/STATUSLEDS4") (class "Default")
      (node (ref "D18") (pin "A") (pinfunction "A_A") (pintype "passive"))
      (node (ref "U6") (pin "1") (pinfunction "QB_1") (pintype "tri_state"))
    )
    (net (code "56") (name "/STATUSLEDS5") (class "Default")
      (node (ref "D19") (pin "A") (pinfunction "A_A") (pintype "passive"))
      (node (ref "U6") (pin "2") (pinfunction "QC_2") (pintype "tri_state"))
    )
    (net (code "57") (name "/STATUSLEDS6") (class "Default")
      (node (ref "D20") (pin "A") (pinfunction "A_A") (pintype "passive"))
      (node (ref "U6") (pin "3") (pinfunction "QD_3") (pintype "tri_state"))
    )
    (net (code "59") (name "3.3V") (class "Default")
      (node (ref "J11") (pin "2") (pinfunction "2_2") (pintype "power_in"))
      (node (ref "J12") (pin "2") (pinfunction "2_2") (pintype "power_in"))
      (node (ref "U2") (pin "16") (pinfunction "VCC_16") (pintype "power_in"))
      (node (ref "U3") (pin "16") (pinfunction "VCC_16") (pintype "power_in"))
      (node (ref "U4") (pin "16") (pinfunction "VCC_16") (pintype "power_in"))
      (node (ref "U5") (pin "16") (pinfunction "VCC_16") (pintype "power_in"))
      (node (ref "U6") (pin "16") (pinfunction "VCC_16") (pintype "power_in"))
    )
    (net (code "60") (name "GND") (class "Default")
      (node (ref "J11") (pin "1") (pinfunction "1_1") (pintype "power_in"))
      (node (ref "J12") (pin "1") (pinfunction "1_1") (pintype "power_in"))
      (node (ref "R1") (pin "P$1") (pinfunction "1_P$1") (pintype "passive"))
      (node (ref "R10") (pin "P$2") (pinfunction "2_P$2") (pintype "passive"))
      (node (ref "R11") (pin "P$2") (pinfunction "2_P$2") (pintype "passive"))
      (node (ref "R12") (pin "P$2") (pinfunction "2_P$2") (pintype "passive"))
      (node (ref "R13") (pin "P$2") (pinfunction "2_P$2") (pintype "passive"))
      (node (ref "R14") (pin "P$2") (pinfunction "2_P$2") (pintype "passive"))
      (node (ref "R15") (pin "P$2") (pinfunction "2_P$2") (pintype "passive"))
      (node (ref "R16") (pin "P$2") (pinfunction "2_P$2") (pintype "passive"))
      (node (ref "R17") (pin "P$2") (pinfunction "2_P$2") (pintype "passive"))
      (node (ref "R18") (pin "P$2") (pinfunction "2_P$2") (pintype "passive"))
      (node (ref "R19") (pin "P$2") (pinfunction "2_P$2") (pintype "passive"))
      (node (ref "R2") (pin "P$1") (pinfunction "1_P$1") (pintype "passive"))
      (node (ref "R20") (pin "P$2") (pinfunction "2_P$2") (pintype "passive"))
      (node (ref "R3") (pin "P$1") (pinfunction "1_P$1") (pintype "passive"))
      (node (ref "R4") (pin "P$1") (pinfunction "1_P$1") (pintype "passive"))
      (node (ref "R5") (pin "P$2") (pinfunction "2_P$2") (pintype "passive"))
      (node (ref "R6") (pin "P$2") (pinfunction "2_P$2") (pintype "passive"))
      (node (ref "R7") (pin "P$2") (pinfunction "2_P$2") (pintype "passive"))
      (node (ref "R8") (pin "P$2") (pinfunction "2_P$2") (pintype "passive"))
      (node (ref "R9") (pin "P$2") (pinfunction "2_P$2") (pintype "passive"))
      (node (ref "S1") (pin "3") (pinfunction "2_3") (pintype "passive"))
      (node (ref "S2") (pin "3") (pinfunction "2_3") (pintype "passive"))
      (node (ref "S3") (pin "3") (pinfunction "2_3") (pintype "passive"))
      (node (ref "S4") (pin "3") (pinfunction "2_3") (pintype "passive"))
      (node (ref "U2") (pin "13") (pinfunction "G_13") (pintype "input"))
      (node (ref "U2") (pin "8") (pinfunction "GND_8") (pintype "power_in"))
      (node (ref "U3") (pin "13") (pinfunction "G_13") (pintype "input"))
      (node (ref "U3") (pin "8") (pinfunction "GND_8") (pintype "power_in"))
      (node (ref "U4") (pin "13") (pinfunction "G_13") (pintype "input"))
      (node (ref "U4") (pin "8") (pinfunction "GND_8") (pintype "power_in"))
      (node (ref "U5") (pin "13") (pinfunction "G_13") (pintype "input"))
      (node (ref "U5") (pin "8") (pinfunction "GND_8") (pintype "power_in"))
      (node (ref "U6") (pin "13") (pinfunction "G_13") (pintype "input"))
      (node (ref "U6") (pin "8") (pinfunction "GND_8") (pintype "power_in"))
    )
    (net (code "61") (name "I2CDATA") (class "Default")
      (node (ref "J11") (pin "3") (pinfunction "3_3") (pintype "passive"))
      (node (ref "J12") (pin "3") (pinfunction "3_3") (pintype "passive"))
      (node (ref "U$1") (pin "19/A5/SCL") (pinfunction "19/A5/SCL_19/A5/SCL") (pintype "bidirectional"))
    )
    (net (code "62") (name "I2CLOCK") (class "Default")
      (node (ref "J11") (pin "4") (pinfunction "4_4") (pintype "passive"))
      (node (ref "J12") (pin "4") (pinfunction "4_4") (pintype "passive"))
      (node (ref "U$1") (pin "18/A4/SDA") (pinfunction "18/A4/SDA_18/A4/SDA") (pintype "bidirectional"))
    )
    (net (code "63") (name "MOSI") (class "Default")
      (node (ref "U$1") (pin "11/MOSI") (pinfunction "11/MOSI_11/MOSI") (pintype "bidirectional"))
      (node (ref "U2") (pin "14") (pinfunction "SER_14") (pintype "input"))
    )
    (net (code "64") (name "Net-(D1-C)") (class "Default")
      (node (ref "D1") (pin "K") (pinfunction "C_K") (pintype "passive"))
      (node (ref "R1") (pin "P$2") (pinfunction "2_P$2") (pintype "passive"))
    )
    (net (code "65") (name "Net-(D2-C)") (class "Default")
      (node (ref "D2") (pin "K") (pinfunction "C_K") (pintype "passive"))
      (node (ref "R2") (pin "P$2") (pinfunction "2_P$2") (pintype "passive"))
    )
    (net (code "66") (name "Net-(D3-C)") (class "Default")
      (node (ref "D3") (pin "K") (pinfunction "C_K") (pintype "passive"))
      (node (ref "R3") (pin "P$2") (pinfunction "2_P$2") (pintype "passive"))
    )
    (net (code "67") (name "Net-(D4-C)") (class "Default")
      (node (ref "D4") (pin "K") (pinfunction "C_K") (pintype "passive"))
      (node (ref "R4") (pin "P$2") (pinfunction "2_P$2") (pintype "passive"))
    )
    (net (code "68") (name "Net-(D5-C)") (class "Default")
      (node (ref "D5") (pin "2") (pinfunction "C_2") (pintype "bidirectional"))
      (node (ref "R5") (pin "P$1") (pinfunction "1_P$1") (pintype "passive"))
    )
    (net (code "69") (name "Net-(D6-C)") (class "Default")
      (node (ref "D6") (pin "2") (pinfunction "C_2") (pintype "bidirectional"))
      (node (ref "R6") (pin "P$1") (pinfunction "1_P$1") (pintype "passive"))
    )
    (net (code "70") (name "Net-(D7-C)") (class "Default")
      (node (ref "D7") (pin "2") (pinfunction "C_2") (pintype "bidirectional"))
      (node (ref "R7") (pin "P$1") (pinfunction "1_P$1") (pintype "passive"))
    )
    (net (code "71") (name "Net-(D8-C)") (class "Default")
      (node (ref "D8") (pin "2") (pinfunction "C_2") (pintype "bidirectional"))
      (node (ref "R8") (pin "P$1") (pinfunction "1_P$1") (pintype "passive"))
    )
    (net (code "72") (name "Net-(D9-C)") (class "Default")
      (node (ref "D9") (pin "2") (pinfunction "C_2") (pintype "bidirectional"))
      (node (ref "R9") (pin "P$1") (pinfunction "1_P$1") (pintype "passive"))
    )
    (net (code "73") (name "Net-(D10-C)") (class "Default")
      (node (ref "D10") (pin "2") (pinfunction "C_2") (pintype "bidirectional"))
      (node (ref "R10") (pin "P$1") (pinfunction "1_P$1") (pintype "passive"))
    )
    (net (code "74") (name "Net-(D11-C)") (class "Default")
      (node (ref "D11") (pin "2") (pinfunction "C_2") (pintype "bidirectional"))
      (node (ref "R11") (pin "P$1") (pinfunction "1_P$1") (pintype "passive"))
    )
    (net (code "75") (name "Net-(D12-C)") (class "Default")
      (node (ref "D12") (pin "2") (pinfunction "C_2") (pintype "bidirectional"))
      (node (ref "R12") (pin "P$1") (pinfunction "1_P$1") (pintype "passive"))
    )
    (net (code "76") (name "Net-(D13-C)") (class "Default")
      (node (ref "D13") (pin "2") (pinfunction "C_2") (pintype "bidirectional"))
      (node (ref "R13") (pin "P$1") (pinfunction "1_P$1") (pintype "passive"))
    )
    (net (code "77") (name "Net-(D14-C)") (class "Default")
      (node (ref "D14") (pin "2") (pinfunction "C_2") (pintype "bidirectional"))
      (node (ref "R14") (pin "P$1") (pinfunction "1_P$1") (pintype "passive"))
    )
    (net (code "78") (name "Net-(D15-C)") (class "Default")
      (node (ref "D15") (pin "K") (pinfunction "C_K") (pintype "passive"))
      (node (ref "R15") (pin "P$1") (pinfunction "1_P$1") (pintype "passive"))
    )
    (net (code "79") (name "Net-(D16-C)") (class "Default")
      (node (ref "D16") (pin "K") (pinfunction "C_K") (pintype "passive"))
      (node (ref "R16") (pin "P$1") (pinfunction "1_P$1") (pintype "passive"))
    )
    (net (code "80") (name "Net-(D17-C)") (class "Default")
      (node (ref "D17") (pin "K") (pinfunction "C_K") (pintype "passive"))
      (node (ref "R17") (pin "P$1") (pinfunction "1_P$1") (pintype "passive"))
    )
    (net (code "81") (name "Net-(D18-C)") (class "Default")
      (node (ref "D18") (pin "K") (pinfunction "C_K") (pintype "passive"))
      (node (ref "R18") (pin "P$1") (pinfunction "1_P$1") (pintype "passive"))
    )
    (net (code "82") (name "Net-(D19-C)") (class "Default")
      (node (ref "D19") (pin "K") (pinfunction "C_K") (pintype "passive"))
      (node (ref "R19") (pin "P$1") (pinfunction "1_P$1") (pintype "passive"))
    )
    (net (code "83") (name "Net-(D20-C)") (class "Default")
      (node (ref "D20") (pin "K") (pinfunction "C_K") (pintype "passive"))
      (node (ref "R20") (pin "P$1") (pinfunction "1_P$1") (pintype "passive"))
    )
    (net (code "84") (name "Net-(U2-QH*)") (class "Default")
      (node (ref "U2") (pin "9") (pinfunction "QH*_9") (pintype "tri_state"))
      (node (ref "U3") (pin "14") (pinfunction "SER_14") (pintype "input"))
    )
    (net (code "85") (name "Net-(U3-QH*)") (class "Default")
      (node (ref "U3") (pin "9") (pinfunction "QH*_9") (pintype "tri_state"))
      (node (ref "U4") (pin "14") (pinfunction "SER_14") (pintype "input"))
    )
    (net (code "86") (name "Net-(U4-QH*)") (class "Default")
      (node (ref "U4") (pin "9") (pinfunction "QH*_9") (pintype "tri_state"))
      (node (ref "U5") (pin "14") (pinfunction "SER_14") (pintype "input"))
    )
    (net (code "87") (name "Net-(U5-QH*)") (class "Default")
      (node (ref "U5") (pin "9") (pinfunction "QH*_9") (pintype "tri_state"))
      (node (ref "U6") (pin "14") (pinfunction "SER_14") (pintype "input"))
    )
    (net (code "88") (name "RCLK") (class "Default")
      (node (ref "U$1") (pin "9/CS") (pinfunction "9/CS_9/CS") (pintype "bidirectional"))
      (node (ref "U2") (pin "12") (pinfunction "RCK_12") (pintype "input"))
      (node (ref "U3") (pin "12") (pinfunction "RCK_12") (pintype "input"))
      (node (ref "U5") (pin "12") (pinfunction "RCK_12") (pintype "input"))
      (node (ref "U6") (pin "12") (pinfunction "RCK_12") (pintype "input"))
    )
    (net (code "89") (name "SCLK") (class "Default")
      (node (ref "U$1") (pin "13/SCK") (pinfunction "13/SCK_13/SCK") (pintype "bidirectional"))
      (node (ref "U2") (pin "11") (pinfunction "SCK_11") (pintype "input"))
      (node (ref "U3") (pin "11") (pinfunction "SCK_11") (pintype "input"))
      (node (ref "U4") (pin "11") (pinfunction "SCK_11") (pintype "input"))
      (node (ref "U5") (pin "11") (pinfunction "SCK_11") (pintype "input"))
      (node (ref "U6") (pin "11") (pinfunction "SCK_11") (pintype "input"))
    )
    (net (code "90") (name "unconnected-(U$1-A21{slash}DAC0-Pad21{slash}DAC0)") (class "Default")
      (node (ref "U$1") (pin "21/DAC0") (pinfunction "A21/DAC0_21/DAC0") (pintype "bidirectional"))
    )
    (net (code "91") (name "unconnected-(U$1-Pad0{slash}RX)") (class "Default")
      (node (ref "U$1") (pin "0/RX") (pinfunction "0/RX_0/RX") (pintype "bidirectional"))
    )
    (net (code "92") (name "unconnected-(U$1-Pad1{slash}TX)") (class "Default")
      (node (ref "U$1") (pin "1/TX") (pinfunction "1/TX_1/TX") (pintype "bidirectional"))
    )
    (net (code "93") (name "unconnected-(U$1-Pad2)") (class "Default")
      (node (ref "U$1") (pin "2") (pinfunction "2_2") (pintype "bidirectional"))
    )
    (net (code "94") (name "unconnected-(U$1-Pad3V3)") (class "Default")
      (node (ref "U$1") (pin "3V3") (pinfunction "3V3_3V3") (pintype "bidirectional"))
    )
    (net (code "95") (name "unconnected-(U$1-Pad3V3_2)") (class "Default")
      (node (ref "U$1") (pin "3V3_2") (pinfunction "3V3_2_3V3_2") (pintype "bidirectional"))
    )
    (net (code "96") (name "unconnected-(U$1-Pad3V3_LO)") (class "Default")
      (node (ref "U$1") (pin "3V3_LO") (pinfunction "3V3_LO_3V3_LO") (pintype "bidirectional"))
    )
    (net (code "97") (name "unconnected-(U$1-Pad7)") (class "Default")
      (node (ref "U$1") (pin "7") (pinfunction "7_7") (pintype "bidirectional"))
    )
    (net (code "98") (name "unconnected-(U$1-Pad8)") (class "Default")
      (node (ref "U$1") (pin "8") (pinfunction "8_8") (pintype "bidirectional"))
    )
    (net (code "99") (name "unconnected-(U$1-Pad10{slash}CS)") (class "Default")
      (node (ref "U$1") (pin "10/CS") (pinfunction "10/CS_10/CS") (pintype "bidirectional"))
    )
    (net (code "100") (name "unconnected-(U$1-Pad12{slash}MISO)") (class "Default")
      (node (ref "U$1") (pin "12/MISO") (pinfunction "12/MISO_12/MISO") (pintype "bidirectional"))
    )
    (net (code "101") (name "unconnected-(U$1-Pad14{slash}A0)") (class "Default")
      (node (ref "U$1") (pin "14/A0") (pinfunction "14/A0_14/A0") (pintype "bidirectional"))
    )
    (net (code "102") (name "unconnected-(U$1-Pad15{slash}A1)") (class "Default")
      (node (ref "U$1") (pin "15/A1") (pinfunction "15/A1_15/A1") (pintype "bidirectional"))
    )
    (net (code "103") (name "unconnected-(U$1-Pad16{slash}A2)") (class "Default")
      (node (ref "U$1") (pin "16/A2") (pinfunction "16/A2_16/A2") (pintype "bidirectional"))
    )
    (net (code "104") (name "unconnected-(U$1-Pad17{slash}A3)") (class "Default")
      (node (ref "U$1") (pin "17/A3") (pinfunction "17/A3_17/A3") (pintype "bidirectional"))
    )
    (net (code "105") (name "unconnected-(U$1-Pad20{slash}A6)") (class "Default")
      (node (ref "U$1") (pin "20/A6") (pinfunction "20/A6_20/A6") (pintype "bidirectional"))
    )
    (net (code "106") (name "unconnected-(U$1-Pad21{slash}A7)") (class "Default")
      (node (ref "U$1") (pin "21/A7") (pinfunction "21/A7_21/A7") (pintype "bidirectional"))
    )
    (net (code "107") (name "unconnected-(U$1-Pad22{slash}A8)") (class "Default")
      (node (ref "U$1") (pin "22/A8") (pinfunction "22/A8_22/A8") (pintype "bidirectional"))
    )
    (net (code "108") (name "unconnected-(U$1-Pad23{slash}A9)") (class "Default")
      (node (ref "U$1") (pin "23/A9") (pinfunction "23/A9_23/A9") (pintype "bidirectional"))
    )
    (net (code "109") (name "unconnected-(U$1-Pad33{slash}A14)") (class "Default")
      (node (ref "U$1") (pin "33/A14") (pinfunction "33/A14_33/A14") (pintype "bidirectional"))
    )
    (net (code "110") (name "unconnected-(U$1-Pad34{slash}A15)") (class "Default")
      (node (ref "U$1") (pin "34/A15") (pinfunction "34/A15_34/A15") (pintype "bidirectional"))
    )
    (net (code "111") (name "unconnected-(U$1-Pad35{slash}A16)") (class "Default")
      (node (ref "U$1") (pin "35/A16") (pinfunction "35/A16_35/A16") (pintype "bidirectional"))
    )
    (net (code "112") (name "unconnected-(U$1-Pad36{slash}A17)") (class "Default")
      (node (ref "U$1") (pin "36/A17") (pinfunction "36/A17_36/A17") (pintype "bidirectional"))
    )
    (net (code "113") (name "unconnected-(U$1-Pad37{slash}A18)") (class "Default")
      (node (ref "U$1") (pin "37/A18") (pinfunction "37/A18_37/A18") (pintype "bidirectional"))
    )
    (net (code "114") (name "unconnected-(U$1-Pad38{slash}A19)") (class "Default")
      (node (ref "U$1") (pin "38/A19") (pinfunction "38/A19_38/A19") (pintype "bidirectional"))
    )
    (net (code "115") (name "unconnected-(U$1-Pad39{slash}A20)") (class "Default")
      (node (ref "U$1") (pin "39/A20") (pinfunction "39/A20_39/A20") (pintype "bidirectional"))
    )
    (net (code "116") (name "unconnected-(U$1-PadA10)") (class "Default")
      (node (ref "U$1") (pin "A10") (pinfunction "A10_A10") (pintype "bidirectional"))
    )
    (net (code "117") (name "unconnected-(U$1-PadA11)") (class "Default")
      (node (ref "U$1") (pin "A11") (pinfunction "A11_A11") (pintype "bidirectional"))
    )
    (net (code "118") (name "unconnected-(U$1-PadA22{slash}DAC1)") (class "Default")
      (node (ref "U$1") (pin "A22/DAC1") (pinfunction "A22/DAC1_A22/DAC1") (pintype "bidirectional"))
    )
    (net (code "119") (name "unconnected-(U$1-PadAGND)") (class "Default")
      (node (ref "U$1") (pin "AGND") (pinfunction "AGND_AGND") (pintype "bidirectional"))
    )
    (net (code "120") (name "unconnected-(U$1-PadAREF)") (class "Default")
      (node (ref "U$1") (pin "AREF") (pinfunction "AREF_AREF") (pintype "bidirectional"))
    )
    (net (code "121") (name "unconnected-(U$1-PadGND)") (class "Default")
      (node (ref "U$1") (pin "GND") (pinfunction "GND_GND") (pintype "bidirectional"))
    )
    (net (code "122") (name "unconnected-(U$1-PadGND2)") (class "Default")
      (node (ref "U$1") (pin "GND2") (pinfunction "GND2_GND2") (pintype "bidirectional"))
    )
    (net (code "123") (name "unconnected-(U$1-PadGND3)") (class "Default")
      (node (ref "U$1") (pin "GND3") (pinfunction "GND3_GND3") (pintype "bidirectional"))
    )
    (net (code "124") (name "unconnected-(U$1-PadPROG)") (class "Default")
      (node (ref "U$1") (pin "PROG") (pinfunction "PROG_PROG") (pintype "bidirectional"))
    )
    (net (code "125") (name "unconnected-(U$1-PadRESET)") (class "Default")
      (node (ref "U$1") (pin "RESET") (pinfunction "RESET_RESET") (pintype "bidirectional"))
    )
    (net (code "126") (name "unconnected-(U$1-PadU5V)") (class "Default")
      (node (ref "U$1") (pin "U5V") (pinfunction "U5V_U5V") (pintype "bidirectional"))
    )
    (net (code "127") (name "unconnected-(U$1-PadUD+)") (class "Default")
      (node (ref "U$1") (pin "UD+") (pinfunction "UD+_UD+") (pintype "bidirectional"))
    )
    (net (code "128") (name "unconnected-(U$1-PadUD-)") (class "Default")
      (node (ref "U$1") (pin "UD-") (pinfunction "UD-_UD-") (pintype "bidirectional"))
    )
    (net (code "129") (name "unconnected-(U$1-PadUGND1)") (class "Default")
      (node (ref "U$1") (pin "UGND1") (pinfunction "UGND1_UGND1") (pintype "bidirectional"))
    )
    (net (code "130") (name "unconnected-(U$1-PadUGND2)") (class "Default")
      (node (ref "U$1") (pin "UGND2") (pinfunction "UGND2_UGND2") (pintype "bidirectional"))
    )
    (net (code "131") (name "unconnected-(U$1-PadVBAT)") (class "Default")
      (node (ref "U$1") (pin "VBAT") (pinfunction "VBAT_VBAT") (pintype "bidirectional"))
    )
    (net (code "132") (name "unconnected-(U$1-PadVIN)") (class "Default")
      (node (ref "U$1") (pin "VIN") (pinfunction "VIN_VIN") (pintype "bidirectional"))
    )
    (net (code "133") (name "unconnected-(U$1-PadVUSB)") (class "Default")
      (node (ref "U$1") (pin "VUSB") (pinfunction "VUSB_VUSB") (pintype "bidirectional"))
    )
    (net (code "134") (name "unconnected-(U2-SCL-Pad10)") (class "Default")
      (node (ref "U2") (pin "10") (pinfunction "SCL_10") (pintype "input"))
    )
    (net (code "135") (name "unconnected-(U3-SCL-Pad10)") (class "Default")
      (node (ref "U3") (pin "10") (pinfunction "SCL_10") (pintype "input"))
    )
    (net (code "136") (name "unconnected-(U4-RCK-Pad12)") (class "Default")
      (node (ref "U4") (pin "12") (pinfunction "RCK_12") (pintype "input"))
    )
    (net (code "137") (name "unconnected-(U4-SCL-Pad10)") (class "Default")
      (node (ref "U4") (pin "10") (pinfunction "SCL_10") (pintype "input"))
    )
    (net (code "138") (name "unconnected-(U5-SCL-Pad10)") (class "Default")
      (node (ref "U5") (pin "10") (pinfunction "SCL_10") (pintype "input"))
    )
    (net (code "139") (name "unconnected-(U6-QH*-Pad9)") (class "Default")
      (node (ref "U6") (pin "9") (pinfunction "QH*_9") (pintype "tri_state"))
    )
    (net (code "140") (name "unconnected-(U6-SCL-Pad10)") (class "Default")
      (node (ref "U6") (pin "10") (pinfunction "SCL_10") (pintype "input"))
    )
  )
)
